# expo_conv_doc.net
KiCad netlist of a schematic drawn in EAGLE
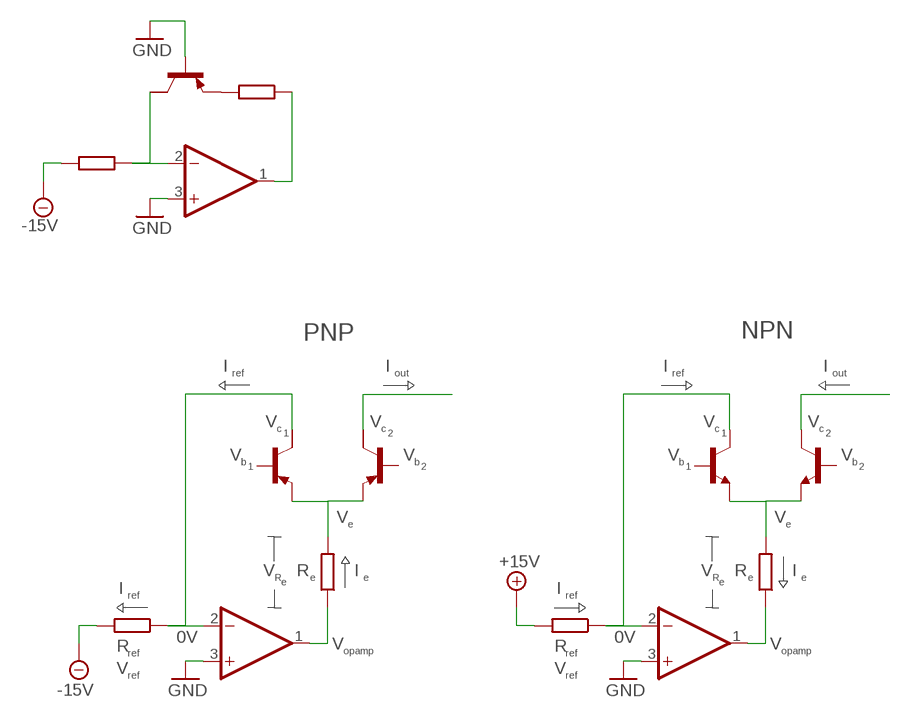
[diagram p0: schematic, sheet 1]

(export (version "E")
  (design (tool "Eeschema 10.0.6"))
  (components
    (comp (ref "IC1")
      (value "TL072D")
      (footprint "eagle-import:SO08")
      (libsource (lib "eagle-import") (part "TL072D"))
    )
    (comp (ref "IC3")
      (value "TL072D")
      (footprint "eagle-import:SO08")
      (libsource (lib "eagle-import") (part "TL072D"))
    )
    (comp (ref "IC4")
      (value "TL072D")
      (footprint "eagle-import:SO08")
      (libsource (lib "eagle-import") (part "TL072D"))
    )
    (comp (ref "R1")
      (value "R-EU_0204/2V")
      (footprint "eagle-import:0204V")
      (libsource (lib "eagle-import") (part "R-EU_0204/2V"))
    )
    (comp (ref "R2")
      (value "R-EU_0204/2V")
      (footprint "eagle-import:0204V")
      (libsource (lib "eagle-import") (part "R-EU_0204/2V"))
    )
    (comp (ref "R5")
      (value "R-EU_0204/2V")
      (footprint "eagle-import:0204V")
      (libsource (lib "eagle-import") (part "R-EU_0204/2V"))
    )
    (comp (ref "R6")
      (value "R-EU_0204/2V")
      (footprint "eagle-import:0204V")
      (libsource (lib "eagle-import") (part "R-EU_0204/2V"))
    )
    (comp (ref "R7")
      (value "R-EU_0204/2V")
      (footprint "eagle-import:0204V")
      (libsource (lib "eagle-import") (part "R-EU_0204/2V"))
    )
    (comp (ref "R8")
      (value "R-EU_0204/2V")
      (footprint "eagle-import:0204V")
      (libsource (lib "eagle-import") (part "R-EU_0204/2V"))
    )
    (comp (ref "T1")
      (value "PNP-TRANSISTIOR-2COLSOT89")
      (footprint "eagle-import:SOT89")
      (libsource (lib "eagle-import") (part "PNP-TRANSISTIOR-2COLSOT89"))
    )
    (comp (ref "T2")
      (value "PNP-TRANSISTIOR-2COLSOT89")
      (footprint "eagle-import:SOT89")
      (libsource (lib "eagle-import") (part "PNP-TRANSISTIOR-2COLSOT89"))
    )
    (comp (ref "T3")
      (value "-NPN-SOT23-EBC")
      (footprint "eagle-import:SOT23-EBC")
      (libsource (lib "eagle-import") (part "-NPN-SOT23-EBC"))
    )
    (comp (ref "T4")
      (value "-NPN-SOT23-EBC")
      (footprint "eagle-import:SOT23-EBC")
      (libsource (lib "eagle-import") (part "-NPN-SOT23-EBC"))
    )
    (comp (ref "T5")
      (value "PNP-TRANSISTIOR-2COLSOT89")
      (footprint "eagle-import:SOT89")
      (libsource (lib "eagle-import") (part "PNP-TRANSISTIOR-2COLSOT89"))
    )
  )
  (nets
    (net (code "1") (name "+15V") (class "Default")
      (node (ref "R8") (pin "2") (pinfunction "2_2") (pintype "passive"))
    )
    (net (code "2") (name "-15V") (class "Default")
      (node (ref "R2") (pin "2") (pinfunction "2_2") (pintype "passive"))
      (node (ref "R6") (pin "2") (pinfunction "2_2") (pintype "passive"))
    )
    (net (code "3") (name "GND") (class "Default")
      (node (ref "IC1") (pin "3") (pinfunction "+IN_3") (pintype "input"))
      (node (ref "IC3") (pin "3") (pinfunction "+IN_3") (pintype "input"))
      (node (ref "IC4") (pin "3") (pinfunction "+IN_3") (pintype "input"))
      (node (ref "T5") (pin "1") (pinfunction "B_1") (pintype "passive"))
    )
    (net (code "4") (name "Net-(IC1A--IN)") (class "Default")
      (node (ref "IC1") (pin "2") (pinfunction "-IN_2") (pintype "input"))
      (node (ref "R2") (pin "1") (pinfunction "1_1") (pintype "passive"))
      (node (ref "T1") (pin "2") (pinfunction "C_2") (pintype "passive"))
    )
    (net (code "5") (name "Net-(IC1A-OUT)") (class "Default")
      (node (ref "IC1") (pin "1") (pinfunction "OUT_1") (pintype "output"))
      (node (ref "R1") (pin "1") (pinfunction "1_1") (pintype "passive"))
    )
    (net (code "6") (name "Net-(IC3A--IN)") (class "Default")
      (node (ref "IC3") (pin "2") (pinfunction "-IN_2") (pintype "input"))
      (node (ref "R6") (pin "1") (pinfunction "1_1") (pintype "passive"))
      (node (ref "T5") (pin "2") (pinfunction "C_2") (pintype "passive"))
    )
    (net (code "7") (name "Net-(IC3A-OUT)") (class "Default")
      (node (ref "IC3") (pin "1") (pinfunction "OUT_1") (pintype "output"))
      (node (ref "R5") (pin "1") (pinfunction "1_1") (pintype "passive"))
    )
    (net (code "8") (name "Net-(IC4A--IN)") (class "Default")
      (node (ref "IC4") (pin "2") (pinfunction "-IN_2") (pintype "input"))
      (node (ref "R8") (pin "1") (pinfunction "1_1") (pintype "passive"))
      (node (ref "T3") (pin "C") (pinfunction "C_C") (pintype "passive"))
    )
    (net (code "9") (name "Net-(IC4A-OUT)") (class "Default")
      (node (ref "IC4") (pin "1") (pinfunction "OUT_1") (pintype "output"))
      (node (ref "R7") (pin "1") (pinfunction "1_1") (pintype "passive"))
    )
    (net (code "10") (name "Net-(R7-Pad2)") (class "Default")
      (node (ref "R7") (pin "2") (pinfunction "2_2") (pintype "passive"))
      (node (ref "T3") (pin "E") (pinfunction "E_E") (pintype "passive"))
      (node (ref "T4") (pin "E") (pinfunction "E_E") (pintype "passive"))
    )
    (net (code "11") (name "Net-(T1-E)") (class "Default")
      (node (ref "R1") (pin "2") (pinfunction "2_2") (pintype "passive"))
      (node (ref "T1") (pin "3") (pinfunction "E_3") (pintype "passive"))
      (node (ref "T2") (pin "3") (pinfunction "E_3") (pintype "passive"))
    )
    (net (code "12") (name "Net-(T5-E)") (class "Default")
      (node (ref "R5") (pin "2") (pinfunction "2_2") (pintype "passive"))
      (node (ref "T5") (pin "3") (pinfunction "E_3") (pintype "passive"))
    )
    (net (code "13") (name "unconnected-(T1-B-Pad1)") (class "Default")
      (node (ref "T1") (pin "1") (pinfunction "B_1") (pintype "passive"))
    )
    (net (code "14") (name "unconnected-(T1-C{slash}-Pad2@1)") (class "Default")
      (node (ref "T1") (pin "2@1") (pinfunction "C/_2@1") (pintype "passive"))
    )
    (net (code "15") (name "unconnected-(T2-B-Pad1)") (class "Default")
      (node (ref "T2") (pin "1") (pinfunction "B_1") (pintype "passive"))
    )
    (net (code "16") (name "unconnected-(T2-C-Pad2)") (class "Default")
      (node (ref "T2") (pin "2") (pinfunction "C_2") (pintype "passive"))
    )
    (net (code "17") (name "unconnected-(T2-C{slash}-Pad2@1)") (class "Default")
      (node (ref "T2") (pin "2@1") (pinfunction "C/_2@1") (pintype "passive"))
    )
    (net (code "18") (name "unconnected-(T3-PadB)") (class "Default")
      (node (ref "T3") (pin "B") (pinfunction "B_B") (pintype "passive"))
    )
    (net (code "19") (name "unconnected-(T4-PadB)") (class "Default")
      (node (ref "T4") (pin "B") (pinfunction "B_B") (pintype "passive"))
    )
    (net (code "20") (name "unconnected-(T4-PadC)") (class "Default")
      (node (ref "T4") (pin "C") (pinfunction "C_C") (pintype "passive"))
    )
    (net (code "21") (name "unconnected-(T5-C{slash}-Pad2@1)") (class "Default")
      (node (ref "T5") (pin "2@1") (pinfunction "C/_2@1") (pintype "passive"))
    )
  )
)
